# Sheet_1_2025-01-22.net
KiCad netlist of a schematic drawn in Altium Designer
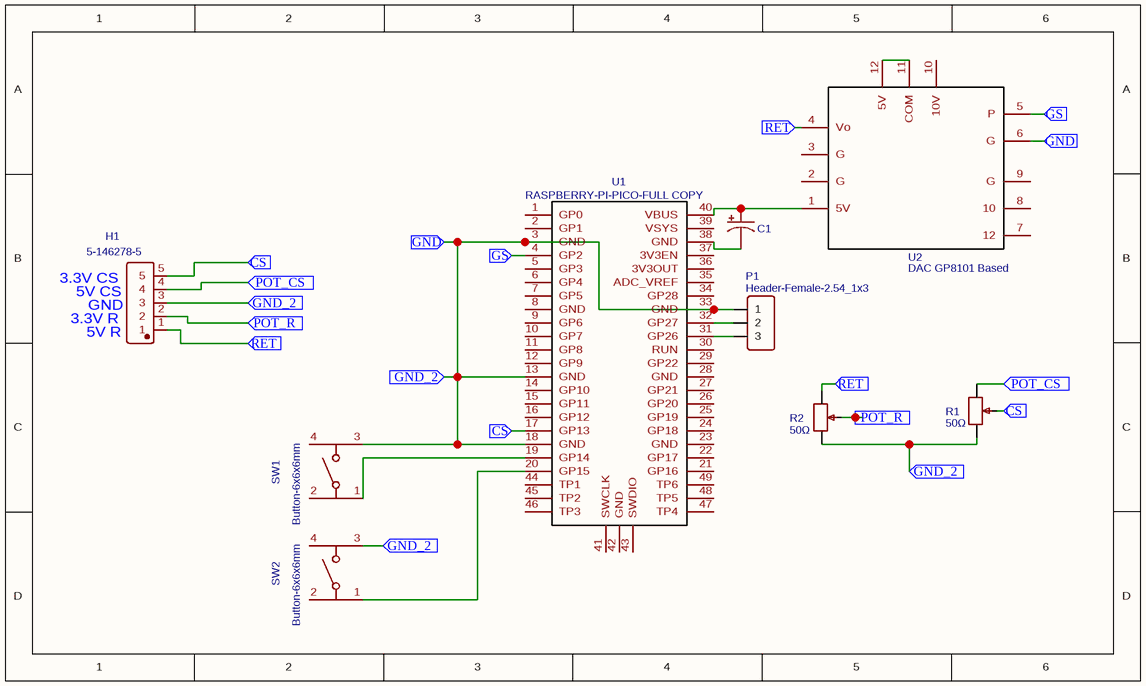
[diagram p0: Sheet_1_2025-01-22.schdoc]

(export (version "E")
  (design (tool "Eeschema 10.0.6"))
  (components
    (comp (ref "C1")
      (value "SPARKFUN-CAPACITORS_CAP_POLPTH1")
      (description "Capacitor Polarized")
      (libsource (lib "altium-import") (part "root_0_SPARKFUN-CAPACITORS_CAP_POLPTH1_"))
    )
    (comp (ref "H1")
      (value "5-146278-5")
      (fields (field (name "MANUFACTURER") "TE Connectivity(泰科电子)") (field (name "CONTRIBUTOR") "lcsc"))
      (libsource (lib "altium-import") (part "root_2_5-146278-5_"))
    )
    (comp (ref "P1")
      (value "Header-Female-2.54_1x3")
      (fields (field (name "MANUFACTURER") "BOOMELE(博穆精密)") (field (name "MANUFACTURER PART") "2.54-1*3P母"))
      (libsource (lib "altium-import") (part "root_0_Header-Female-2.54_1x3_"))
    )
    (comp (ref "R1")
      (value "50Ω")
      (fields
        (field (name "MANUFACTURER") "ReliaPro")
        (field (name "MANUFACTURER PART") "Precision potentiometer 3296W/50ohm")
      )
      (libsource (lib "altium-import") (part "root_2_50Ω_"))
    )
    (comp (ref "R2")
      (value "50Ω")
      (fields
        (field (name "MANUFACTURER") "ReliaPro")
        (field (name "MANUFACTURER PART") "Precision potentiometer 3296W/50ohm")
      )
      (libsource (lib "altium-import") (part "root_2_50Ω_"))
    )
    (comp (ref "SW1")
      (value "Button-6x6x6mm")
      (fields
        (field (name "MANUFACTURER") "BBJ")
        (field (name "MANUFACTURER PART") "Switch,6*6*6Plastic head,260G, 0.25mm,Straight line")
      )
      (libsource (lib "altium-import") (part "root_2_Button-6x6x6mm_"))
    )
    (comp (ref "SW2")
      (value "Button-6x6x6mm")
      (fields
        (field (name "MANUFACTURER") "BBJ")
        (field (name "MANUFACTURER PART") "Switch,6*6*6Plastic head,260G, 0.25mm,Straight line")
      )
      (libsource (lib "altium-import") (part "root_2_Button-6x6x6mm_"))
    )
    (comp (ref "U1")
      (value "RASPBERRY-PI-PICO-FULL COPY")
      (fields
        (field (name "MANUFACTURER") "Raspberry Pi Foundation")
        (field (name "MANUFACTURER PART") "Raspberry Pi Pico")
        (field (name "CONTRIBUTOR") "yakimovroman1982")
      )
      (libsource (lib "altium-import") (part "root_0_RASPBERRY-PI-PICO-FULL COPY_"))
    )
    (comp (ref "U2")
      (value "DAC GP8101 Based")
      (fields (field (name "CONTRIBUTOR") "19031250"))
      (libsource (lib "altium-import") (part "root_0_DAC GP8101 Based_"))
    )
  )
  (nets
    (net (code "1") (name "/CS") (class "Default")
      (node (ref "H1") (pin "5") (pinfunction "5_5") (pintype "passive"))
      (node (ref "R1") (pin "2") (pinfunction "2_2") (pintype "passive"))
      (node (ref "U1") (pin "17") (pinfunction "GP13_17") (pintype "passive"))
    )
    (net (code "2") (name "/GND") (class "Default")
      (node (ref "H1") (pin "3") (pinfunction "3_3") (pintype "passive"))
      (node (ref "P1") (pin "1") (pinfunction "1_1") (pintype "passive"))
      (node (ref "R1") (pin "1") (pinfunction "1_1") (pintype "passive"))
      (node (ref "R2") (pin "1") (pinfunction "1_1") (pintype "passive"))
      (node (ref "SW1") (pin "3") (pinfunction "3_3") (pintype "passive"))
      (node (ref "SW2") (pin "3") (pinfunction "3_3") (pintype "passive"))
      (node (ref "U1") (pin "13") (pinfunction "GND_13") (pintype "passive"))
      (node (ref "U1") (pin "18") (pinfunction "GND_18") (pintype "passive"))
      (node (ref "U1") (pin "3") (pinfunction "GND_3") (pintype "passive"))
      (node (ref "U1") (pin "33") (pinfunction "GND_33") (pintype "passive"))
      (node (ref "U2") (pin "6") (pinfunction "G_6") (pintype "passive"))
    )
    (net (code "3") (name "/GS") (class "Default")
      (node (ref "U1") (pin "4") (pinfunction "GP2_4") (pintype "passive"))
      (node (ref "U2") (pin "5") (pinfunction "P_5") (pintype "passive"))
    )
    (net (code "4") (name "/POT_CS") (class "Default")
      (node (ref "H1") (pin "4") (pinfunction "4_4") (pintype "passive"))
      (node (ref "R1") (pin "3") (pinfunction "3_3") (pintype "passive"))
    )
    (net (code "5") (name "/POT_R") (class "Default")
      (node (ref "H1") (pin "2") (pinfunction "2_2") (pintype "passive"))
      (node (ref "R2") (pin "2") (pinfunction "2_2") (pintype "passive"))
    )
    (net (code "6") (name "/RET") (class "Default")
      (node (ref "H1") (pin "1") (pinfunction "1_1") (pintype "passive"))
      (node (ref "R2") (pin "3") (pinfunction "3_3") (pintype "passive"))
      (node (ref "U2") (pin "4") (pinfunction "Vo_4") (pintype "passive"))
    )
    (net (code "7") (name "Net-(C1-+)") (class "Default")
      (node (ref "C1") (pin "1") (pinfunction "+_1") (pintype "passive"))
      (node (ref "U1") (pin "40") (pinfunction "VBUS_40") (pintype "passive"))
      (node (ref "U2") (pin "1") (pinfunction "5V_1") (pintype "passive"))
    )
    (net (code "8") (name "Net-(C1--)") (class "Default")
      (node (ref "C1") (pin "2") (pinfunction "-_2") (pintype "passive"))
      (node (ref "U1") (pin "38") (pinfunction "GND_38") (pintype "passive"))
    )
    (net (code "9") (name "Net-(U1-GP14)") (class "Default")
      (node (ref "SW1") (pin "1") (pinfunction "1_1") (pintype "passive"))
      (node (ref "U1") (pin "19") (pinfunction "GP14_19") (pintype "passive"))
    )
    (net (code "10") (name "Net-(U1-GP15)") (class "Default")
      (node (ref "SW2") (pin "1") (pinfunction "1_1") (pintype "passive"))
      (node (ref "U1") (pin "20") (pinfunction "GP15_20") (pintype "passive"))
    )
    (net (code "11") (name "Net-(U1-GP26)") (class "Default")
      (node (ref "P1") (pin "3") (pinfunction "3_3") (pintype "passive"))
      (node (ref "U1") (pin "31") (pinfunction "GP26_31") (pintype "passive"))
    )
    (net (code "12") (name "Net-(U1-GP27)") (class "Default")
      (node (ref "P1") (pin "2") (pinfunction "2_2") (pintype "passive"))
      (node (ref "U1") (pin "32") (pinfunction "GP27_32") (pintype "passive"))
    )
    (net (code "13") (name "Net-(U2-COM)") (class "Default")
      (node (ref "U2") (pin "11") (pinfunction "COM_11") (pintype "passive"))
      (node (ref "U2") (pin "12") (pinfunction "5V_12") (pintype "passive"))
    )
    (net (code "14") (name "unconnected-(SW1-Pad2)") (class "Default")
      (node (ref "SW1") (pin "2") (pinfunction "2_2") (pintype "passive"))
    )
    (net (code "15") (name "unconnected-(SW1-Pad4)") (class "Default")
      (node (ref "SW1") (pin "4") (pinfunction "4_4") (pintype "passive"))
    )
    (net (code "16") (name "unconnected-(SW2-Pad2)") (class "Default")
      (node (ref "SW2") (pin "2") (pinfunction "2_2") (pintype "passive"))
    )
    (net (code "17") (name "unconnected-(SW2-Pad4)") (class "Default")
      (node (ref "SW2") (pin "4") (pinfunction "4_4") (pintype "passive"))
    )
    (net (code "18") (name "unconnected-(U1-3V3EN-Pad37)") (class "Default")
      (node (ref "U1") (pin "37") (pinfunction "3V3EN_37") (pintype "passive"))
    )
    (net (code "19") (name "unconnected-(U1-3V3OUT-Pad36)") (class "Default")
      (node (ref "U1") (pin "36") (pinfunction "3V3OUT_36") (pintype "passive"))
    )
    (net (code "20") (name "unconnected-(U1-ADC_VREF-Pad35)") (class "Default")
      (node (ref "U1") (pin "35") (pinfunction "ADC_VREF_35") (pintype "passive"))
    )
    (net (code "21") (name "unconnected-(U1-GND-Pad8)") (class "Default")
      (node (ref "U1") (pin "8") (pinfunction "GND_8") (pintype "passive"))
    )
    (net (code "22") (name "unconnected-(U1-GND-Pad23)") (class "Default")
      (node (ref "U1") (pin "23") (pinfunction "GND_23") (pintype "passive"))
    )
    (net (code "23") (name "unconnected-(U1-GND-Pad28)") (class "Default")
      (node (ref "U1") (pin "28") (pinfunction "GND_28") (pintype "passive"))
    )
    (net (code "24") (name "unconnected-(U1-GND-Pad42)") (class "Default")
      (node (ref "U1") (pin "42") (pinfunction "GND_42") (pintype "passive"))
    )
    (net (code "25") (name "unconnected-(U1-GP0-Pad1)") (class "Default")
      (node (ref "U1") (pin "1") (pinfunction "GP0_1") (pintype "passive"))
    )
    (net (code "26") (name "unconnected-(U1-GP1-Pad2)") (class "Default")
      (node (ref "U1") (pin "2") (pinfunction "GP1_2") (pintype "passive"))
    )
    (net (code "27") (name "unconnected-(U1-GP3-Pad5)") (class "Default")
      (node (ref "U1") (pin "5") (pinfunction "GP3_5") (pintype "passive"))
    )
    (net (code "28") (name "unconnected-(U1-GP4-Pad6)") (class "Default")
      (node (ref "U1") (pin "6") (pinfunction "GP4_6") (pintype "passive"))
    )
    (net (code "29") (name "unconnected-(U1-GP5-Pad7)") (class "Default")
      (node (ref "U1") (pin "7") (pinfunction "GP5_7") (pintype "passive"))
    )
    (net (code "30") (name "unconnected-(U1-GP6-Pad9)") (class "Default")
      (node (ref "U1") (pin "9") (pinfunction "GP6_9") (pintype "passive"))
    )
    (net (code "31") (name "unconnected-(U1-GP7-Pad10)") (class "Default")
      (node (ref "U1") (pin "10") (pinfunction "GP7_10") (pintype "passive"))
    )
    (net (code "32") (name "unconnected-(U1-GP8-Pad11)") (class "Default")
      (node (ref "U1") (pin "11") (pinfunction "GP8_11") (pintype "passive"))
    )
    (net (code "33") (name "unconnected-(U1-GP9-Pad12)") (class "Default")
      (node (ref "U1") (pin "12") (pinfunction "GP9_12") (pintype "passive"))
    )
    (net (code "34") (name "unconnected-(U1-GP10-Pad14)") (class "Default")
      (node (ref "U1") (pin "14") (pinfunction "GP10_14") (pintype "passive"))
    )
    (net (code "35") (name "unconnected-(U1-GP11-Pad15)") (class "Default")
      (node (ref "U1") (pin "15") (pinfunction "GP11_15") (pintype "passive"))
    )
    (net (code "36") (name "unconnected-(U1-GP12-Pad16)") (class "Default")
      (node (ref "U1") (pin "16") (pinfunction "GP12_16") (pintype "passive"))
    )
    (net (code "37") (name "unconnected-(U1-GP16-Pad21)") (class "Default")
      (node (ref "U1") (pin "21") (pinfunction "GP16_21") (pintype "passive"))
    )
    (net (code "38") (name "unconnected-(U1-GP17-Pad22)") (class "Default")
      (node (ref "U1") (pin "22") (pinfunction "GP17_22") (pintype "passive"))
    )
    (net (code "39") (name "unconnected-(U1-GP18-Pad24)") (class "Default")
      (node (ref "U1") (pin "24") (pinfunction "GP18_24") (pintype "passive"))
    )
    (net (code "40") (name "unconnected-(U1-GP19-Pad25)") (class "Default")
      (node (ref "U1") (pin "25") (pinfunction "GP19_25") (pintype "passive"))
    )
    (net (code "41") (name "unconnected-(U1-GP20-Pad26)") (class "Default")
      (node (ref "U1") (pin "26") (pinfunction "GP20_26") (pintype "passive"))
    )
    (net (code "42") (name "unconnected-(U1-GP21-Pad27)") (class "Default")
      (node (ref "U1") (pin "27") (pinfunction "GP21_27") (pintype "passive"))
    )
    (net (code "43") (name "unconnected-(U1-GP22-Pad29)") (class "Default")
      (node (ref "U1") (pin "29") (pinfunction "GP22_29") (pintype "passive"))
    )
    (net (code "44") (name "unconnected-(U1-GP28-Pad34)") (class "Default")
      (node (ref "U1") (pin "34") (pinfunction "GP28_34") (pintype "passive"))
    )
    (net (code "45") (name "unconnected-(U1-RUN-Pad30)") (class "Default")
      (node (ref "U1") (pin "30") (pinfunction "RUN_30") (pintype "passive"))
    )
    (net (code "46") (name "unconnected-(U1-SWCLK-Pad41)") (class "Default")
      (node (ref "U1") (pin "41") (pinfunction "SWCLK_41") (pintype "passive"))
    )
    (net (code "47") (name "unconnected-(U1-SWDIO-Pad43)") (class "Default")
      (node (ref "U1") (pin "43") (pinfunction "SWDIO_43") (pintype "passive"))
    )
    (net (code "48") (name "unconnected-(U1-TP1-Pad44)") (class "Default")
      (node (ref "U1") (pin "44") (pinfunction "TP1_44") (pintype "passive"))
    )
    (net (code "49") (name "unconnected-(U1-TP2-Pad45)") (class "Default")
      (node (ref "U1") (pin "45") (pinfunction "TP2_45") (pintype "passive"))
    )
    (net (code "50") (name "unconnected-(U1-TP3-Pad46)") (class "Default")
      (node (ref "U1") (pin "46") (pinfunction "TP3_46") (pintype "passive"))
    )
    (net (code "51") (name "unconnected-(U1-TP4-Pad47)") (class "Default")
      (node (ref "U1") (pin "47") (pinfunction "TP4_47") (pintype "passive"))
    )
    (net (code "52") (name "unconnected-(U1-TP5-Pad48)") (class "Default")
      (node (ref "U1") (pin "48") (pinfunction "TP5_48") (pintype "passive"))
    )
    (net (code "53") (name "unconnected-(U1-TP6-Pad49)") (class "Default")
      (node (ref "U1") (pin "49") (pinfunction "TP6_49") (pintype "passive"))
    )
    (net (code "54") (name "unconnected-(U1-VSYS-Pad39)") (class "Default")
      (node (ref "U1") (pin "39") (pinfunction "VSYS_39") (pintype "passive"))
    )
    (net (code "55") (name "unconnected-(U2-10-Pad8)") (class "Default")
      (node (ref "U2") (pin "8") (pinfunction "10_8") (pintype "passive"))
    )
    (net (code "56") (name "unconnected-(U2-10V-Pad10)") (class "Default")
      (node (ref "U2") (pin "10") (pinfunction "10V_10") (pintype "passive"))
    )
    (net (code "57") (name "unconnected-(U2-12-Pad7)") (class "Default")
      (node (ref "U2") (pin "7") (pinfunction "12_7") (pintype "passive"))
    )
    (net (code "58") (name "unconnected-(U2-G-Pad2)") (class "Default")
      (node (ref "U2") (pin "2") (pinfunction "G_2") (pintype "passive"))
    )
    (net (code "59") (name "unconnected-(U2-G-Pad3)") (class "Default")
      (node (ref "U2") (pin "3") (pinfunction "G_3") (pintype "passive"))
    )
    (net (code "60") (name "unconnected-(U2-G-Pad9)") (class "Default")
      (node (ref "U2") (pin "9") (pinfunction "G_9") (pintype "passive"))
    )
  )
)
